# cominer_amp.net
KiCad netlist of a schematic drawn in EAGLE
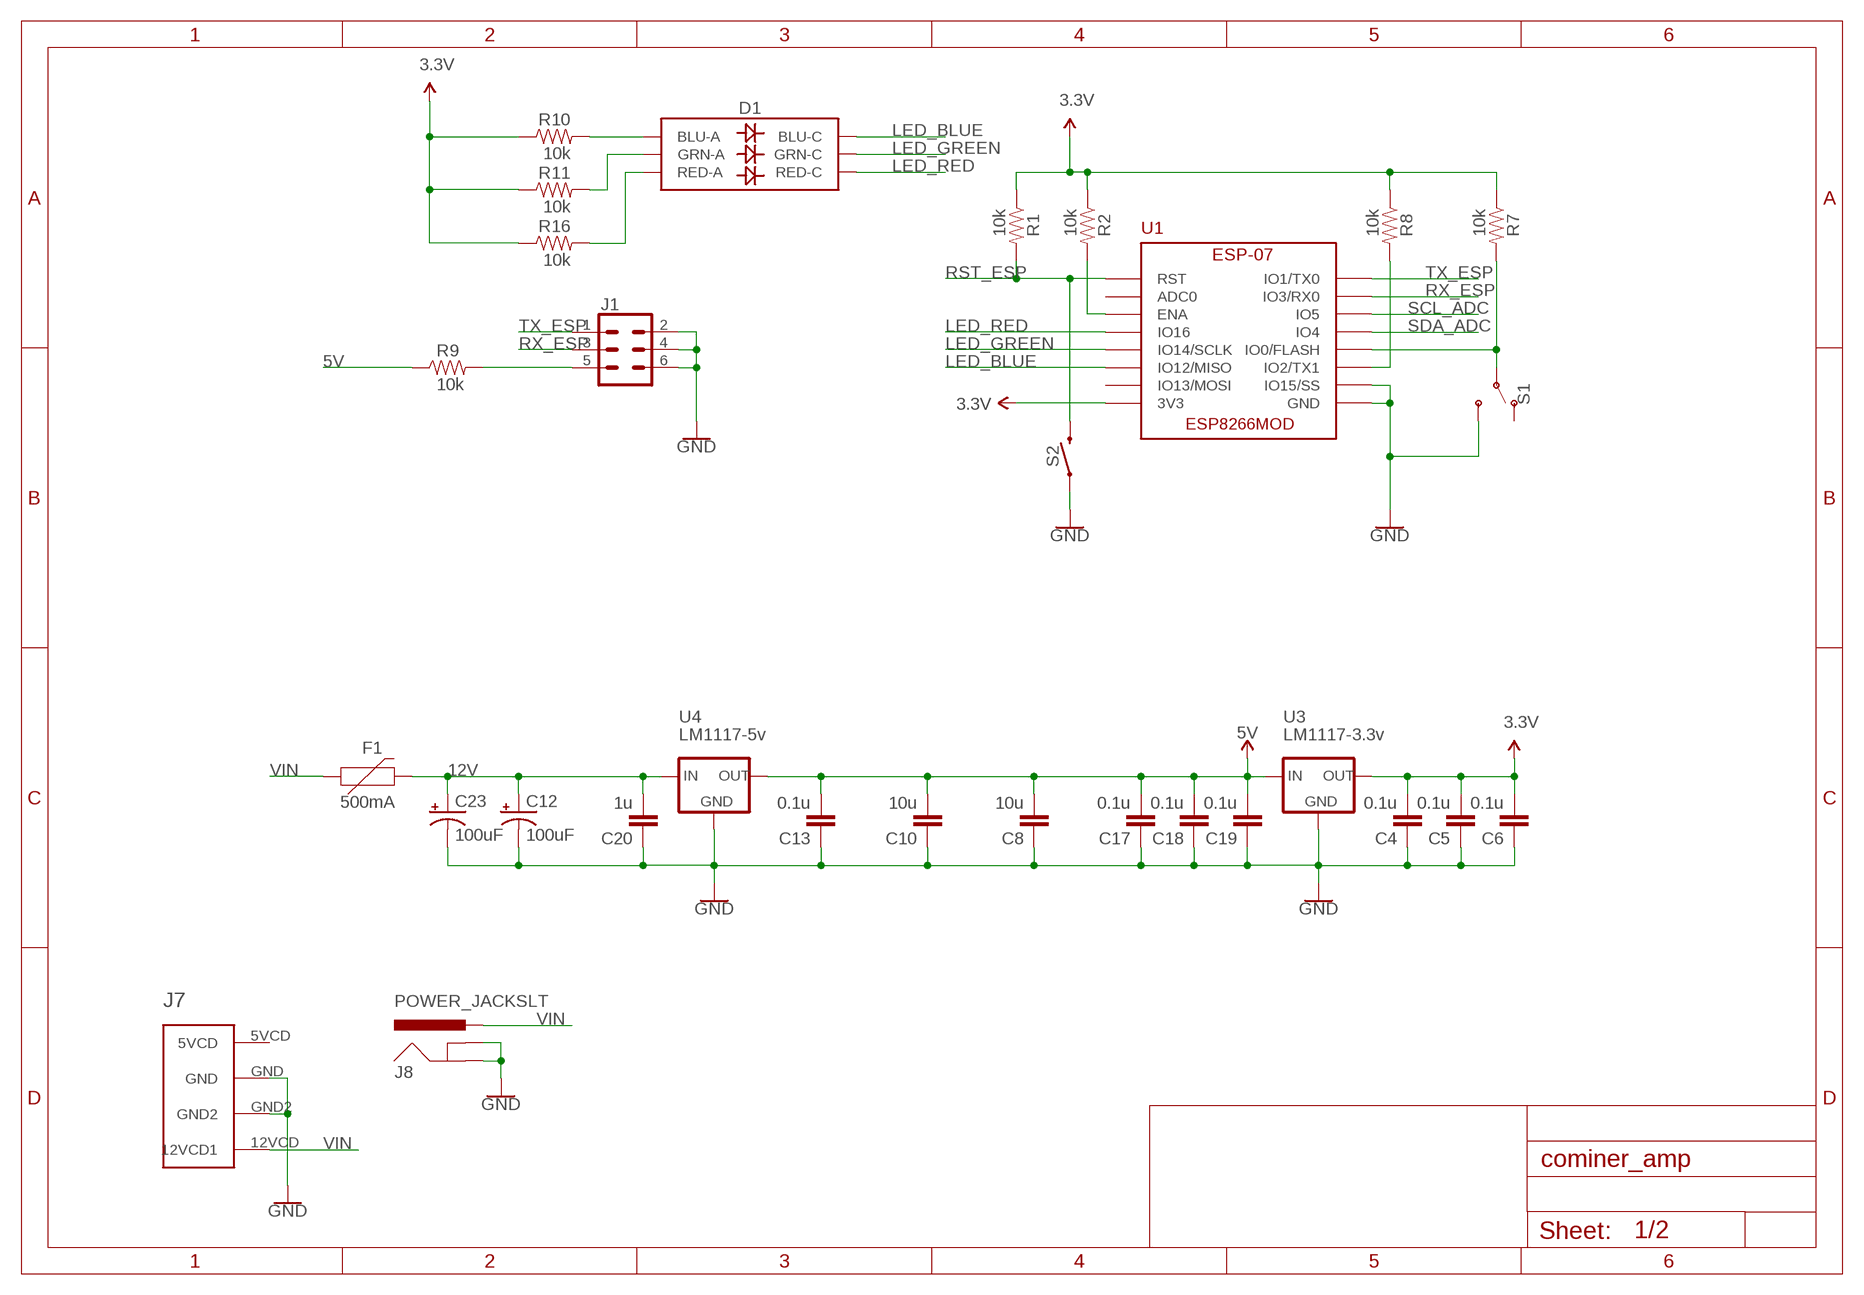
[diagram p0: schematic, sheet 1]
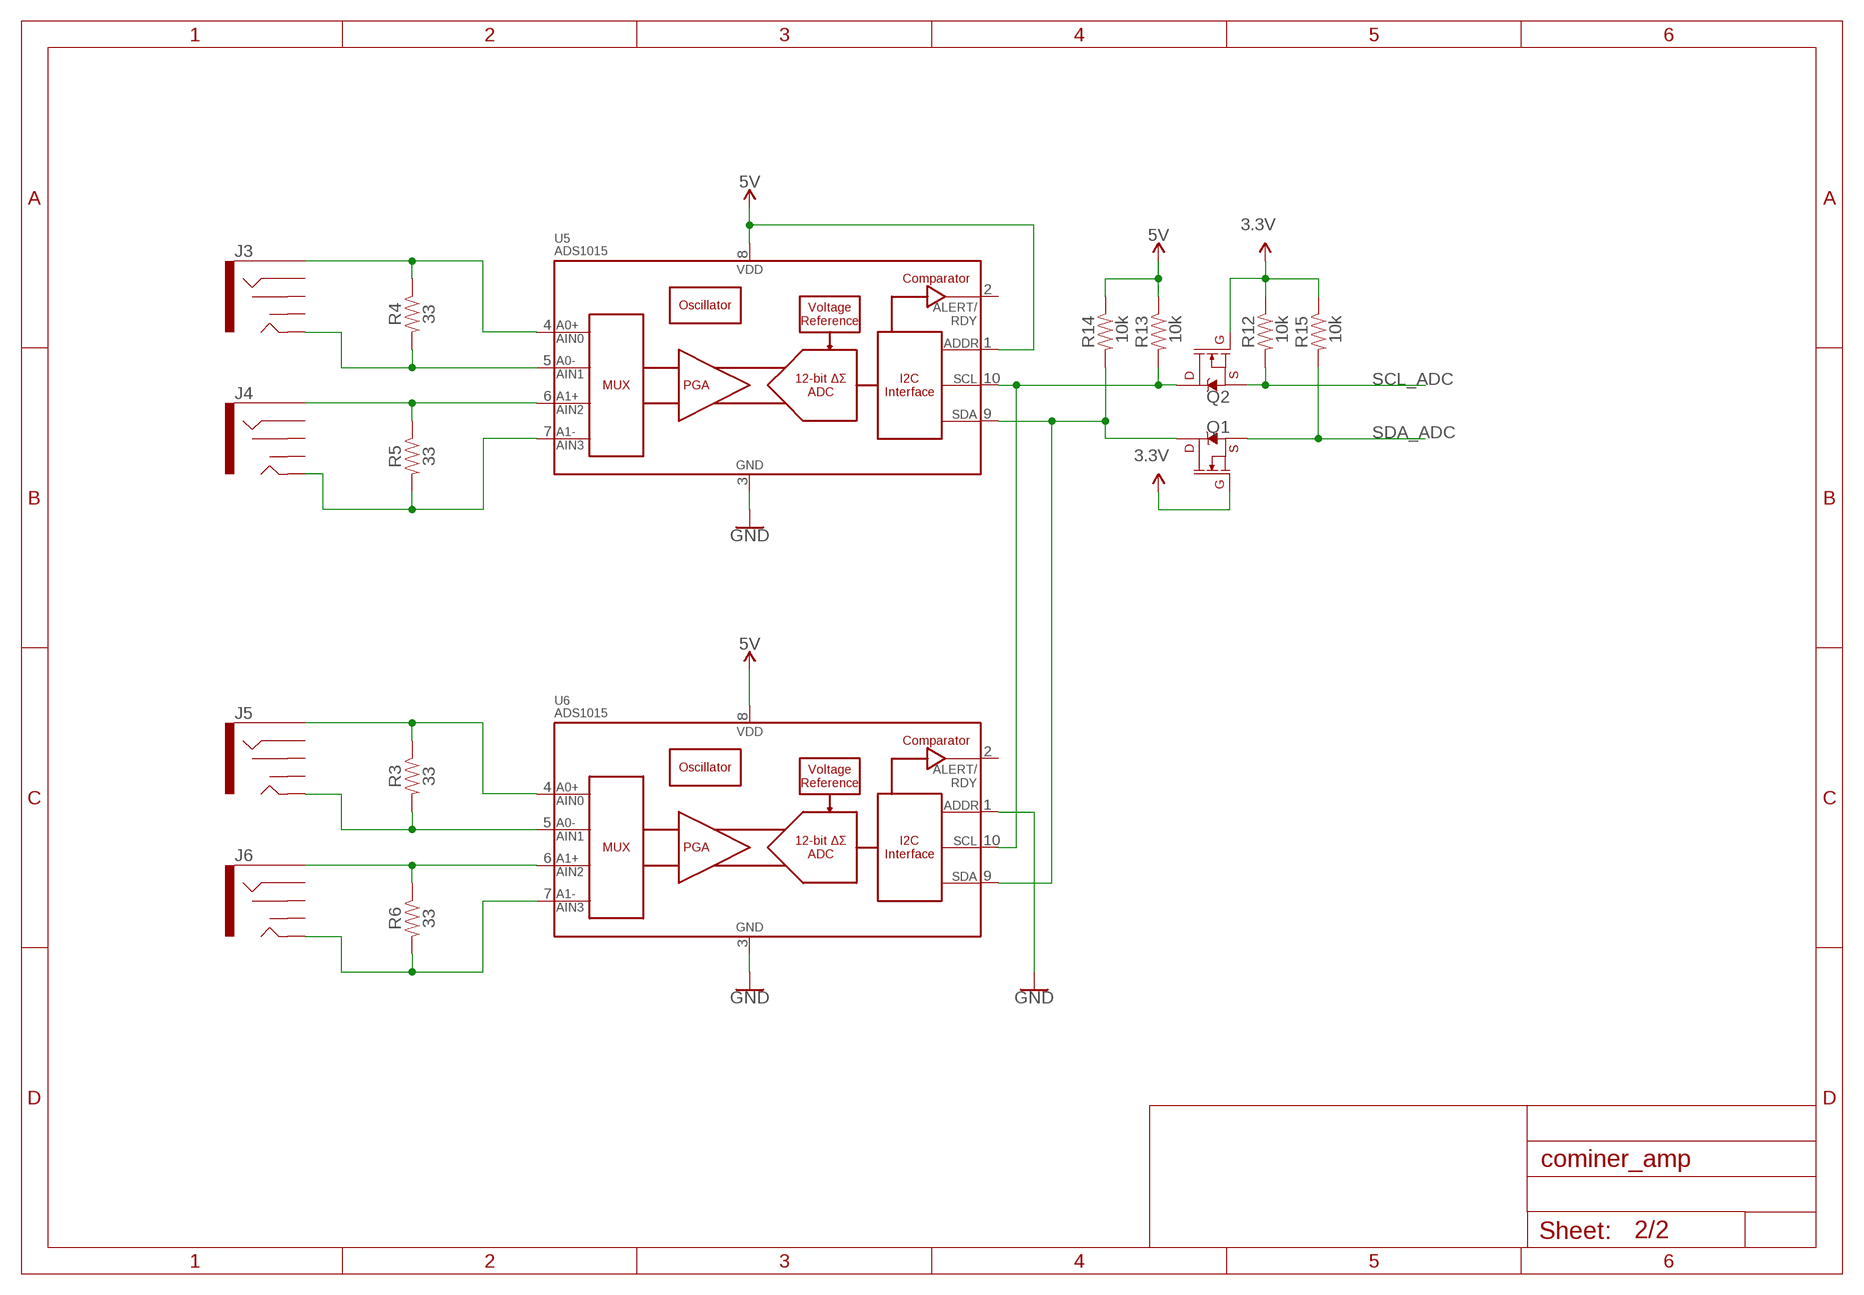
[diagram p1: schematic, sheet 2]

(export (version "E")
  (design (tool "Eeschema 10.0.6"))
  (components
    (comp (ref "C4")
      (value "0.1u")
      (footprint "eagle-import:0805")
      (libsource (lib "eagle-import") (part "CAP-0805"))
    )
    (comp (ref "C5")
      (value "0.1u")
      (footprint "eagle-import:0805")
      (libsource (lib "eagle-import") (part "CAP-0805"))
    )
    (comp (ref "C6")
      (value "0.1u")
      (footprint "eagle-import:0805")
      (libsource (lib "eagle-import") (part "CAP-0805"))
    )
    (comp (ref "C8")
      (value "10u")
      (footprint "eagle-import:0805")
      (libsource (lib "eagle-import") (part "CAP-0805"))
    )
    (comp (ref "C10")
      (value "10u")
      (footprint "eagle-import:0805")
      (libsource (lib "eagle-import") (part "CAP-0805"))
    )
    (comp (ref "C12")
      (value "100uF")
      (footprint "eagle-import:PANASONIC_D")
      (libsource (lib "eagle-import") (part "100UF-POLAR-25V-20%(ELEC)"))
    )
    (comp (ref "C13")
      (value "0.1u")
      (footprint "eagle-import:0805")
      (libsource (lib "eagle-import") (part "CAP-0805"))
    )
    (comp (ref "C17")
      (value "0.1u")
      (footprint "eagle-import:0805")
      (libsource (lib "eagle-import") (part "CAP-0805"))
    )
    (comp (ref "C18")
      (value "0.1u")
      (footprint "eagle-import:0805")
      (libsource (lib "eagle-import") (part "CAP-0805"))
    )
    (comp (ref "C19")
      (value "0.1u")
      (footprint "eagle-import:0805")
      (libsource (lib "eagle-import") (part "CAP-0805"))
    )
    (comp (ref "C20")
      (value "1u")
      (footprint "eagle-import:0805")
      (libsource (lib "eagle-import") (part "CAP-0805"))
    )
    (comp (ref "C23")
      (value "100uF")
      (footprint "eagle-import:PANASONIC_D")
      (libsource (lib "eagle-import") (part "100UF-POLAR-25V-20%(ELEC)"))
    )
    (comp (ref "D1")
      (value "LED-RGBNO_IC")
      (footprint "eagle-import:LED-TRICOLOR-5050")
      (libsource (lib "eagle-import") (part "LED-RGBNO_IC"))
    )
    (comp (ref "F1")
      (value "500mA")
      (footprint "eagle-import:1812")
      (libsource (lib "eagle-import") (part "PPTC_16V_2.5A"))
    )
    (comp (ref "J1")
      (value "CONN_03X2SHROUD")
      (footprint "eagle-import:2X3-SHROUDED")
      (libsource (lib "eagle-import") (part "CONN_03X2SHROUD"))
    )
    (comp (ref "J7")
      (value "MOLEX-CPU-POWER")
      (footprint "eagle-import:MOLEX-5.08-4PIN")
      (libsource (lib "eagle-import") (part "MOLEX-CPU-POWER"))
    )
    (comp (ref "J8")
      (value "POWER_JACKSLT")
      (footprint "eagle-import:POWER_JACK_SLOT")
      (libsource (lib "eagle-import") (part "POWER_JACKSLT"))
    )
    (comp (ref "R1")
      (value "10k")
      (footprint "eagle-import:0805")
      (libsource (lib "eagle-import") (part "RESISTOR0805"))
    )
    (comp (ref "R2")
      (value "10k")
      (footprint "eagle-import:0805")
      (libsource (lib "eagle-import") (part "RESISTOR0805"))
    )
    (comp (ref "R7")
      (value "10k")
      (footprint "eagle-import:0805")
      (libsource (lib "eagle-import") (part "RESISTOR0805"))
    )
    (comp (ref "R8")
      (value "10k")
      (footprint "eagle-import:0805")
      (libsource (lib "eagle-import") (part "RESISTOR0805"))
    )
    (comp (ref "R9")
      (value "10k")
      (footprint "eagle-import:0805")
      (libsource (lib "eagle-import") (part "RESISTOR0805"))
    )
    (comp (ref "R10")
      (value "10k")
      (footprint "eagle-import:0805")
      (libsource (lib "eagle-import") (part "RESISTOR0805"))
    )
    (comp (ref "R11")
      (value "10k")
      (footprint "eagle-import:0805")
      (libsource (lib "eagle-import") (part "RESISTOR0805"))
    )
    (comp (ref "R16")
      (value "10k")
      (footprint "eagle-import:0805")
      (libsource (lib "eagle-import") (part "RESISTOR0805"))
    )
    (comp (ref "S1")
      (value "SWITCH-SPDT-SMD-RIGHT-ANGLE")
      (footprint "eagle-import:SWITCH_SPST_SMD_A")
      (libsource (lib "eagle-import") (part "SWITCH-SPDT-SMD-RIGHT-ANGLE"))
    )
    (comp (ref "S2")
      (value "MOMENTARY-SWITCH-SPST-SMD-6.0X3.5MM")
      (footprint "eagle-import:TACTILE_SWITCH_SMD_6.0X3.5MM")
      (libsource (lib "eagle-import") (part "MOMENTARY-SWITCH-SPST-SMD-6.0X3.5MM"))
    )
    (comp (ref "U1")
      (value "ESP-07")
      (footprint "eagle-import:ESP-07")
      (libsource (lib "eagle-import") (part "ESP-07"))
    )
    (comp (ref "U3")
      (value "LM1117-3.3v")
      (footprint "eagle-import:SOT223")
      (libsource (lib "eagle-import") (part "V_REG_LD1117VXXLD1117-SMD"))
    )
    (comp (ref "U4")
      (value "LM1117-5v")
      (footprint "eagle-import:SOT223")
      (libsource (lib "eagle-import") (part "V_REG_LD1117VXXLD1117-SMD"))
    )
    (comp (ref "J3")
      (value "AUDIO_JACK_3.5MM_PTH")
      (footprint "eagle-import:AUDIO-JACK")
      (libsource (lib "eagle-import") (part "AUDIO_JACK_3.5MM_PTH"))
    )
    (comp (ref "J4")
      (value "AUDIO_JACK_3.5MM_PTH")
      (footprint "eagle-import:AUDIO-JACK")
      (libsource (lib "eagle-import") (part "AUDIO_JACK_3.5MM_PTH"))
    )
    (comp (ref "J5")
      (value "AUDIO_JACK_3.5MM_PTH")
      (footprint "eagle-import:AUDIO-JACK")
      (libsource (lib "eagle-import") (part "AUDIO_JACK_3.5MM_PTH"))
    )
    (comp (ref "J6")
      (value "AUDIO_JACK_3.5MM_PTH")
      (footprint "eagle-import:AUDIO-JACK")
      (libsource (lib "eagle-import") (part "AUDIO_JACK_3.5MM_PTH"))
    )
    (comp (ref "Q1")
      (value "BSS138")
      (footprint "eagle-import:SOT23-3")
      (libsource (lib "eagle-import") (part "MOSFET-NCH-BSS138"))
    )
    (comp (ref "Q2")
      (value "BSS138")
      (footprint "eagle-import:SOT23-3")
      (libsource (lib "eagle-import") (part "MOSFET-NCH-BSS138"))
    )
    (comp (ref "R3")
      (value "33")
      (footprint "eagle-import:0805")
      (libsource (lib "eagle-import") (part "RESISTOR0805"))
    )
    (comp (ref "R4")
      (value "33")
      (footprint "eagle-import:0805")
      (libsource (lib "eagle-import") (part "RESISTOR0805"))
    )
    (comp (ref "R5")
      (value "33")
      (footprint "eagle-import:0805")
      (libsource (lib "eagle-import") (part "RESISTOR0805"))
    )
    (comp (ref "R6")
      (value "33")
      (footprint "eagle-import:0805")
      (libsource (lib "eagle-import") (part "RESISTOR0805"))
    )
    (comp (ref "R12")
      (value "10k")
      (footprint "eagle-import:0805")
      (libsource (lib "eagle-import") (part "RESISTOR0805"))
    )
    (comp (ref "R13")
      (value "10k")
      (footprint "eagle-import:0805")
      (libsource (lib "eagle-import") (part "RESISTOR0805"))
    )
    (comp (ref "R14")
      (value "10k")
      (footprint "eagle-import:0805")
      (libsource (lib "eagle-import") (part "RESISTOR0805"))
    )
    (comp (ref "R15")
      (value "10k")
      (footprint "eagle-import:0805")
      (libsource (lib "eagle-import") (part "RESISTOR0805"))
    )
    (comp (ref "U5")
      (value "ADS1015")
      (footprint "eagle-import:MSOP10")
      (libsource (lib "eagle-import") (part "ADS1015"))
    )
    (comp (ref "U6")
      (value "ADS1015")
      (footprint "eagle-import:MSOP10")
      (libsource (lib "eagle-import") (part "ADS1015"))
    )
  )
  (nets
    (net (code "1") (name "3.3V") (class "Default")
      (node (ref "C4") (pin "2") (pinfunction "2_2") (pintype "passive"))
      (node (ref "C5") (pin "2") (pinfunction "2_2") (pintype "passive"))
      (node (ref "C6") (pin "2") (pinfunction "2_2") (pintype "passive"))
      (node (ref "Q1") (pin "1") (pinfunction "G_1") (pintype "bidirectional"))
      (node (ref "Q2") (pin "1") (pinfunction "G_1") (pintype "bidirectional"))
      (node (ref "R1") (pin "1") (pinfunction "1_1") (pintype "passive"))
      (node (ref "R10") (pin "1") (pinfunction "1_1") (pintype "passive"))
      (node (ref "R11") (pin "1") (pinfunction "1_1") (pintype "passive"))
      (node (ref "R12") (pin "1") (pinfunction "1_1") (pintype "passive"))
      (node (ref "R15") (pin "1") (pinfunction "1_1") (pintype "passive"))
      (node (ref "R16") (pin "1") (pinfunction "1_1") (pintype "passive"))
      (node (ref "R2") (pin "1") (pinfunction "1_1") (pintype "passive"))
      (node (ref "R7") (pin "1") (pinfunction "1_1") (pintype "passive"))
      (node (ref "R8") (pin "1") (pinfunction "1_1") (pintype "passive"))
      (node (ref "U1") (pin "3V3") (pinfunction "3V3_3V3") (pintype "power_in"))
      (node (ref "U3") (pin "2") (pinfunction "OUT_2") (pintype "passive"))
    )
    (net (code "2") (name "5V") (class "Default")
      (node (ref "C10") (pin "2") (pinfunction "2_2") (pintype "passive"))
      (node (ref "C13") (pin "2") (pinfunction "2_2") (pintype "passive"))
      (node (ref "C17") (pin "2") (pinfunction "2_2") (pintype "passive"))
      (node (ref "C18") (pin "2") (pinfunction "2_2") (pintype "passive"))
      (node (ref "C19") (pin "2") (pinfunction "2_2") (pintype "passive"))
      (node (ref "C8") (pin "2") (pinfunction "2_2") (pintype "passive"))
      (node (ref "R13") (pin "1") (pinfunction "1_1") (pintype "passive"))
      (node (ref "R14") (pin "1") (pinfunction "1_1") (pintype "passive"))
      (node (ref "R9") (pin "1") (pinfunction "1_1") (pintype "passive"))
      (node (ref "U3") (pin "3") (pinfunction "IN_3") (pintype "input"))
      (node (ref "U4") (pin "2") (pinfunction "OUT_2") (pintype "passive"))
      (node (ref "U5") (pin "1") (pinfunction "ADDR_1") (pintype "bidirectional"))
      (node (ref "U5") (pin "8") (pinfunction "VDD_8") (pintype "bidirectional"))
      (node (ref "U6") (pin "8") (pinfunction "VDD_8") (pintype "bidirectional"))
    )
    (net (code "3") (name "12V") (class "Default")
      (node (ref "C12") (pin "+") (pinfunction "+_+") (pintype "passive"))
      (node (ref "C20") (pin "2") (pinfunction "2_2") (pintype "passive"))
      (node (ref "C23") (pin "+") (pinfunction "+_+") (pintype "passive"))
      (node (ref "F1") (pin "2") (pinfunction "2_2") (pintype "bidirectional"))
      (node (ref "U4") (pin "3") (pinfunction "IN_3") (pintype "input"))
    )
    (net (code "4") (name "GND") (class "Default")
      (node (ref "C10") (pin "1") (pinfunction "1_1") (pintype "passive"))
      (node (ref "C12") (pin "-") (pinfunction "-_-") (pintype "passive"))
      (node (ref "C13") (pin "1") (pinfunction "1_1") (pintype "passive"))
      (node (ref "C17") (pin "1") (pinfunction "1_1") (pintype "passive"))
      (node (ref "C18") (pin "1") (pinfunction "1_1") (pintype "passive"))
      (node (ref "C19") (pin "1") (pinfunction "1_1") (pintype "passive"))
      (node (ref "C20") (pin "1") (pinfunction "1_1") (pintype "passive"))
      (node (ref "C23") (pin "-") (pinfunction "-_-") (pintype "passive"))
      (node (ref "C4") (pin "1") (pinfunction "1_1") (pintype "passive"))
      (node (ref "C5") (pin "1") (pinfunction "1_1") (pintype "passive"))
      (node (ref "C6") (pin "1") (pinfunction "1_1") (pintype "passive"))
      (node (ref "C8") (pin "1") (pinfunction "1_1") (pintype "passive"))
      (node (ref "J1") (pin "2") (pinfunction "2_2") (pintype "bidirectional"))
      (node (ref "J1") (pin "4") (pinfunction "4_4") (pintype "bidirectional"))
      (node (ref "J1") (pin "6") (pinfunction "6_6") (pintype "bidirectional"))
      (node (ref "J7") (pin "GND") (pinfunction "GND_GND") (pintype "bidirectional"))
      (node (ref "J7") (pin "GND2") (pinfunction "GND2_GND2") (pintype "bidirectional"))
      (node (ref "J8") (pin "GND@1") (pinfunction "GNDBREAK_GND@1") (pintype "bidirectional"))
      (node (ref "J8") (pin "GND@2") (pinfunction "GND_GND@2") (pintype "bidirectional"))
      (node (ref "S1") (pin "3") (pinfunction "S_3") (pintype "passive"))
      (node (ref "S2") (pin "1") (pinfunction "1_1") (pintype "passive"))
      (node (ref "U1") (pin "GND") (pinfunction "GND_GND") (pintype "power_in"))
      (node (ref "U1") (pin "IO15") (pinfunction "IO15/SS_IO15") (pintype "bidirectional"))
      (node (ref "U3") (pin "1") (pinfunction "GND_1") (pintype "input"))
      (node (ref "U4") (pin "1") (pinfunction "GND_1") (pintype "input"))
      (node (ref "U5") (pin "3") (pinfunction "VSS_3") (pintype "bidirectional"))
      (node (ref "U6") (pin "1") (pinfunction "ADDR_1") (pintype "bidirectional"))
      (node (ref "U6") (pin "3") (pinfunction "VSS_3") (pintype "bidirectional"))
    )
    (net (code "5") (name "LED_BLUE") (class "Default")
      (node (ref "D1") (pin "4") (pinfunction "BLU-C_4") (pintype "bidirectional"))
      (node (ref "U1") (pin "IO12") (pinfunction "IO12/MISO_IO12") (pintype "bidirectional"))
    )
    (net (code "6") (name "LED_GREEN") (class "Default")
      (node (ref "D1") (pin "6") (pinfunction "GRN-C_6") (pintype "bidirectional"))
      (node (ref "U1") (pin "IO14") (pinfunction "IO14/SCLK_IO14") (pintype "bidirectional"))
    )
    (net (code "7") (name "LED_RED") (class "Default")
      (node (ref "D1") (pin "5") (pinfunction "RED-C_5") (pintype "bidirectional"))
      (node (ref "U1") (pin "I016") (pinfunction "IO16_I016") (pintype "bidirectional"))
    )
    (net (code "8") (name "Net-(D1-BLU-A)") (class "Default")
      (node (ref "D1") (pin "3") (pinfunction "BLU-A_3") (pintype "bidirectional"))
      (node (ref "R10") (pin "2") (pinfunction "2_2") (pintype "passive"))
    )
    (net (code "9") (name "Net-(D1-GRN-A)") (class "Default")
      (node (ref "D1") (pin "1") (pinfunction "GRN-A_1") (pintype "bidirectional"))
      (node (ref "R11") (pin "2") (pinfunction "2_2") (pintype "passive"))
    )
    (net (code "10") (name "Net-(D1-RED-A)") (class "Default")
      (node (ref "D1") (pin "2") (pinfunction "RED-A_2") (pintype "bidirectional"))
      (node (ref "R16") (pin "2") (pinfunction "2_2") (pintype "passive"))
    )
    (net (code "11") (name "Net-(J1-Pad5)") (class "Default")
      (node (ref "J1") (pin "5") (pinfunction "5_5") (pintype "bidirectional"))
      (node (ref "R9") (pin "2") (pinfunction "2_2") (pintype "passive"))
    )
    (net (code "12") (name "Net-(Q1-D)") (class "Default")
      (node (ref "Q1") (pin "3") (pinfunction "D_3") (pintype "bidirectional"))
      (node (ref "R14") (pin "2") (pinfunction "2_2") (pintype "passive"))
      (node (ref "U5") (pin "9") (pinfunction "SDA_9") (pintype "bidirectional"))
      (node (ref "U6") (pin "9") (pinfunction "SDA_9") (pintype "bidirectional"))
    )
    (net (code "13") (name "Net-(Q2-D)") (class "Default")
      (node (ref "Q2") (pin "3") (pinfunction "D_3") (pintype "bidirectional"))
      (node (ref "R13") (pin "2") (pinfunction "2_2") (pintype "passive"))
      (node (ref "U5") (pin "10") (pinfunction "SCL_10") (pintype "bidirectional"))
      (node (ref "U6") (pin "10") (pinfunction "SCL_10") (pintype "bidirectional"))
    )
    (net (code "14") (name "Net-(R2-Pad2)") (class "Default")
      (node (ref "R2") (pin "2") (pinfunction "2_2") (pintype "passive"))
      (node (ref "U1") (pin "ENA") (pinfunction "ENA_ENA") (pintype "input"))
    )
    (net (code "15") (name "Net-(S1-P)") (class "Default")
      (node (ref "R7") (pin "2") (pinfunction "2_2") (pintype "passive"))
      (node (ref "S1") (pin "2") (pinfunction "P_2") (pintype "passive"))
      (node (ref "U1") (pin "IO0") (pinfunction "IO0/FLASH_IO0") (pintype "bidirectional"))
    )
    (net (code "16") (name "Net-(U1-IO2{slash}TX1)") (class "Default")
      (node (ref "R8") (pin "2") (pinfunction "2_2") (pintype "passive"))
      (node (ref "U1") (pin "IO2") (pinfunction "IO2/TX1_IO2") (pintype "bidirectional"))
    )
    (net (code "17") (name "Net-(U5-AIN0)") (class "Default")
      (node (ref "J3") (pin "SLEEVE") (pinfunction "SLEEVE_SLEEVE") (pintype "bidirectional"))
      (node (ref "R4") (pin "1") (pinfunction "1_1") (pintype "passive"))
      (node (ref "U5") (pin "4") (pinfunction "AIN0_4") (pintype "bidirectional"))
    )
    (net (code "18") (name "Net-(U5-AIN1)") (class "Default")
      (node (ref "J3") (pin "TIP") (pinfunction "TIP_TIP") (pintype "bidirectional"))
      (node (ref "R4") (pin "2") (pinfunction "2_2") (pintype "passive"))
      (node (ref "U5") (pin "5") (pinfunction "AIN1_5") (pintype "bidirectional"))
    )
    (net (code "19") (name "Net-(U5-AIN2)") (class "Default")
      (node (ref "J4") (pin "SLEEVE") (pinfunction "SLEEVE_SLEEVE") (pintype "bidirectional"))
      (node (ref "R5") (pin "1") (pinfunction "1_1") (pintype "passive"))
      (node (ref "U5") (pin "6") (pinfunction "AIN2_6") (pintype "bidirectional"))
    )
    (net (code "20") (name "Net-(U5-AIN3)") (class "Default")
      (node (ref "J4") (pin "TIP") (pinfunction "TIP_TIP") (pintype "bidirectional"))
      (node (ref "R5") (pin "2") (pinfunction "2_2") (pintype "passive"))
      (node (ref "U5") (pin "7") (pinfunction "AIN3_7") (pintype "bidirectional"))
    )
    (net (code "21") (name "Net-(U6-AIN0)") (class "Default")
      (node (ref "J5") (pin "SLEEVE") (pinfunction "SLEEVE_SLEEVE") (pintype "bidirectional"))
      (node (ref "R3") (pin "1") (pinfunction "1_1") (pintype "passive"))
      (node (ref "U6") (pin "4") (pinfunction "AIN0_4") (pintype "bidirectional"))
    )
    (net (code "22") (name "Net-(U6-AIN1)") (class "Default")
      (node (ref "J5") (pin "TIP") (pinfunction "TIP_TIP") (pintype "bidirectional"))
      (node (ref "R3") (pin "2") (pinfunction "2_2") (pintype "passive"))
      (node (ref "U6") (pin "5") (pinfunction "AIN1_5") (pintype "bidirectional"))
    )
    (net (code "23") (name "Net-(U6-AIN2)") (class "Default")
      (node (ref "J6") (pin "SLEEVE") (pinfunction "SLEEVE_SLEEVE") (pintype "bidirectional"))
      (node (ref "R6") (pin "1") (pinfunction "1_1") (pintype "passive"))
      (node (ref "U6") (pin "6") (pinfunction "AIN2_6") (pintype "bidirectional"))
    )
    (net (code "24") (name "Net-(U6-AIN3)") (class "Default")
      (node (ref "J6") (pin "TIP") (pinfunction "TIP_TIP") (pintype "bidirectional"))
      (node (ref "R6") (pin "2") (pinfunction "2_2") (pintype "passive"))
      (node (ref "U6") (pin "7") (pinfunction "AIN3_7") (pintype "bidirectional"))
    )
    (net (code "25") (name "RST_ESP") (class "Default")
      (node (ref "R1") (pin "2") (pinfunction "2_2") (pintype "passive"))
      (node (ref "S2") (pin "2") (pinfunction "2_2") (pintype "passive"))
      (node (ref "U1") (pin "RST") (pinfunction "RST_RST") (pintype "input"))
    )
    (net (code "26") (name "RX_ESP") (class "Default")
      (node (ref "J1") (pin "3") (pinfunction "3_3") (pintype "bidirectional"))
      (node (ref "U1") (pin "RX0") (pinfunction "IO3/RX0_RX0") (pintype "bidirectional"))
    )
    (net (code "27") (name "SCL_ADC") (class "Default")
      (node (ref "Q2") (pin "2") (pinfunction "S_2") (pintype "bidirectional"))
      (node (ref "R12") (pin "2") (pinfunction "2_2") (pintype "passive"))
      (node (ref "U1") (pin "IO5") (pinfunction "IO5_IO5") (pintype "bidirectional"))
    )
    (net (code "28") (name "SDA_ADC") (class "Default")
      (node (ref "Q1") (pin "2") (pinfunction "S_2") (pintype "bidirectional"))
      (node (ref "R15") (pin "2") (pinfunction "2_2") (pintype "passive"))
      (node (ref "U1") (pin "IO4") (pinfunction "IO4_IO4") (pintype "bidirectional"))
    )
    (net (code "29") (name "TX_ESP") (class "Default")
      (node (ref "J1") (pin "1") (pinfunction "1_1") (pintype "bidirectional"))
      (node (ref "U1") (pin "TX0") (pinfunction "IO1/TX0_TX0") (pintype "bidirectional"))
    )
    (net (code "30") (name "VIN") (class "Default")
      (node (ref "F1") (pin "1") (pinfunction "1_1") (pintype "bidirectional"))
      (node (ref "J7") (pin "12VCD") (pinfunction "12VCD1_12VCD") (pintype "bidirectional"))
      (node (ref "J8") (pin "PWR") (pinfunction "PWR_PWR") (pintype "bidirectional"))
    )
    (net (code "31") (name "unconnected-(J3-PadRING)") (class "Default")
      (node (ref "J3") (pin "RING") (pinfunction "RING_RING") (pintype "bidirectional"))
    )
    (net (code "32") (name "unconnected-(J3-PadRSH)") (class "Default")
      (node (ref "J3") (pin "RSH") (pinfunction "RSH_RSH") (pintype "bidirectional"))
    )
    (net (code "33") (name "unconnected-(J3-PadTSH)") (class "Default")
      (node (ref "J3") (pin "TSH") (pinfunction "TSH_TSH") (pintype "bidirectional"))
    )
    (net (code "34") (name "unconnected-(J4-PadRING)") (class "Default")
      (node (ref "J4") (pin "RING") (pinfunction "RING_RING") (pintype "bidirectional"))
    )
    (net (code "35") (name "unconnected-(J4-PadRSH)") (class "Default")
      (node (ref "J4") (pin "RSH") (pinfunction "RSH_RSH") (pintype "bidirectional"))
    )
    (net (code "36") (name "unconnected-(J4-PadTSH)") (class "Default")
      (node (ref "J4") (pin "TSH") (pinfunction "TSH_TSH") (pintype "bidirectional"))
    )
    (net (code "37") (name "unconnected-(J5-PadRING)") (class "Default")
      (node (ref "J5") (pin "RING") (pinfunction "RING_RING") (pintype "bidirectional"))
    )
    (net (code "38") (name "unconnected-(J5-PadRSH)") (class "Default")
      (node (ref "J5") (pin "RSH") (pinfunction "RSH_RSH") (pintype "bidirectional"))
    )
    (net (code "39") (name "unconnected-(J5-PadTSH)") (class "Default")
      (node (ref "J5") (pin "TSH") (pinfunction "TSH_TSH") (pintype "bidirectional"))
    )
    (net (code "40") (name "unconnected-(J6-PadRING)") (class "Default")
      (node (ref "J6") (pin "RING") (pinfunction "RING_RING") (pintype "bidirectional"))
    )
    (net (code "41") (name "unconnected-(J6-PadRSH)") (class "Default")
      (node (ref "J6") (pin "RSH") (pinfunction "RSH_RSH") (pintype "bidirectional"))
    )
    (net (code "42") (name "unconnected-(J6-PadTSH)") (class "Default")
      (node (ref "J6") (pin "TSH") (pinfunction "TSH_TSH") (pintype "bidirectional"))
    )
    (net (code "43") (name "unconnected-(J7-Pad5VCD)") (class "Default")
      (node (ref "J7") (pin "5VCD") (pinfunction "5VCD_5VCD") (pintype "bidirectional"))
    )
    (net (code "44") (name "unconnected-(S1-O-Pad1)") (class "Default")
      (node (ref "S1") (pin "1") (pinfunction "O_1") (pintype "passive"))
    )
    (net (code "45") (name "unconnected-(U1-ADC0-PadADC)") (class "Default")
      (node (ref "U1") (pin "ADC") (pinfunction "ADC0_ADC") (pintype "input"))
    )
    (net (code "46") (name "unconnected-(U1-IO13{slash}MOSI-PadIO13)") (class "Default")
      (node (ref "U1") (pin "IO13") (pinfunction "IO13/MOSI_IO13") (pintype "bidirectional"))
    )
    (net (code "47") (name "unconnected-(U5-ALERT{slash}RDY-Pad2)") (class "Default")
      (node (ref "U5") (pin "2") (pinfunction "ALERT/RDY_2") (pintype "bidirectional"))
    )
    (net (code "48") (name "unconnected-(U6-ALERT{slash}RDY-Pad2)") (class "Default")
      (node (ref "U6") (pin "2") (pinfunction "ALERT/RDY_2") (pintype "bidirectional"))
    )
  )
)
